# ProPrj___2024-09-21_20-05-29_2024-09-27.net
KiCad netlist of a schematic drawn in EasyEDA Pro
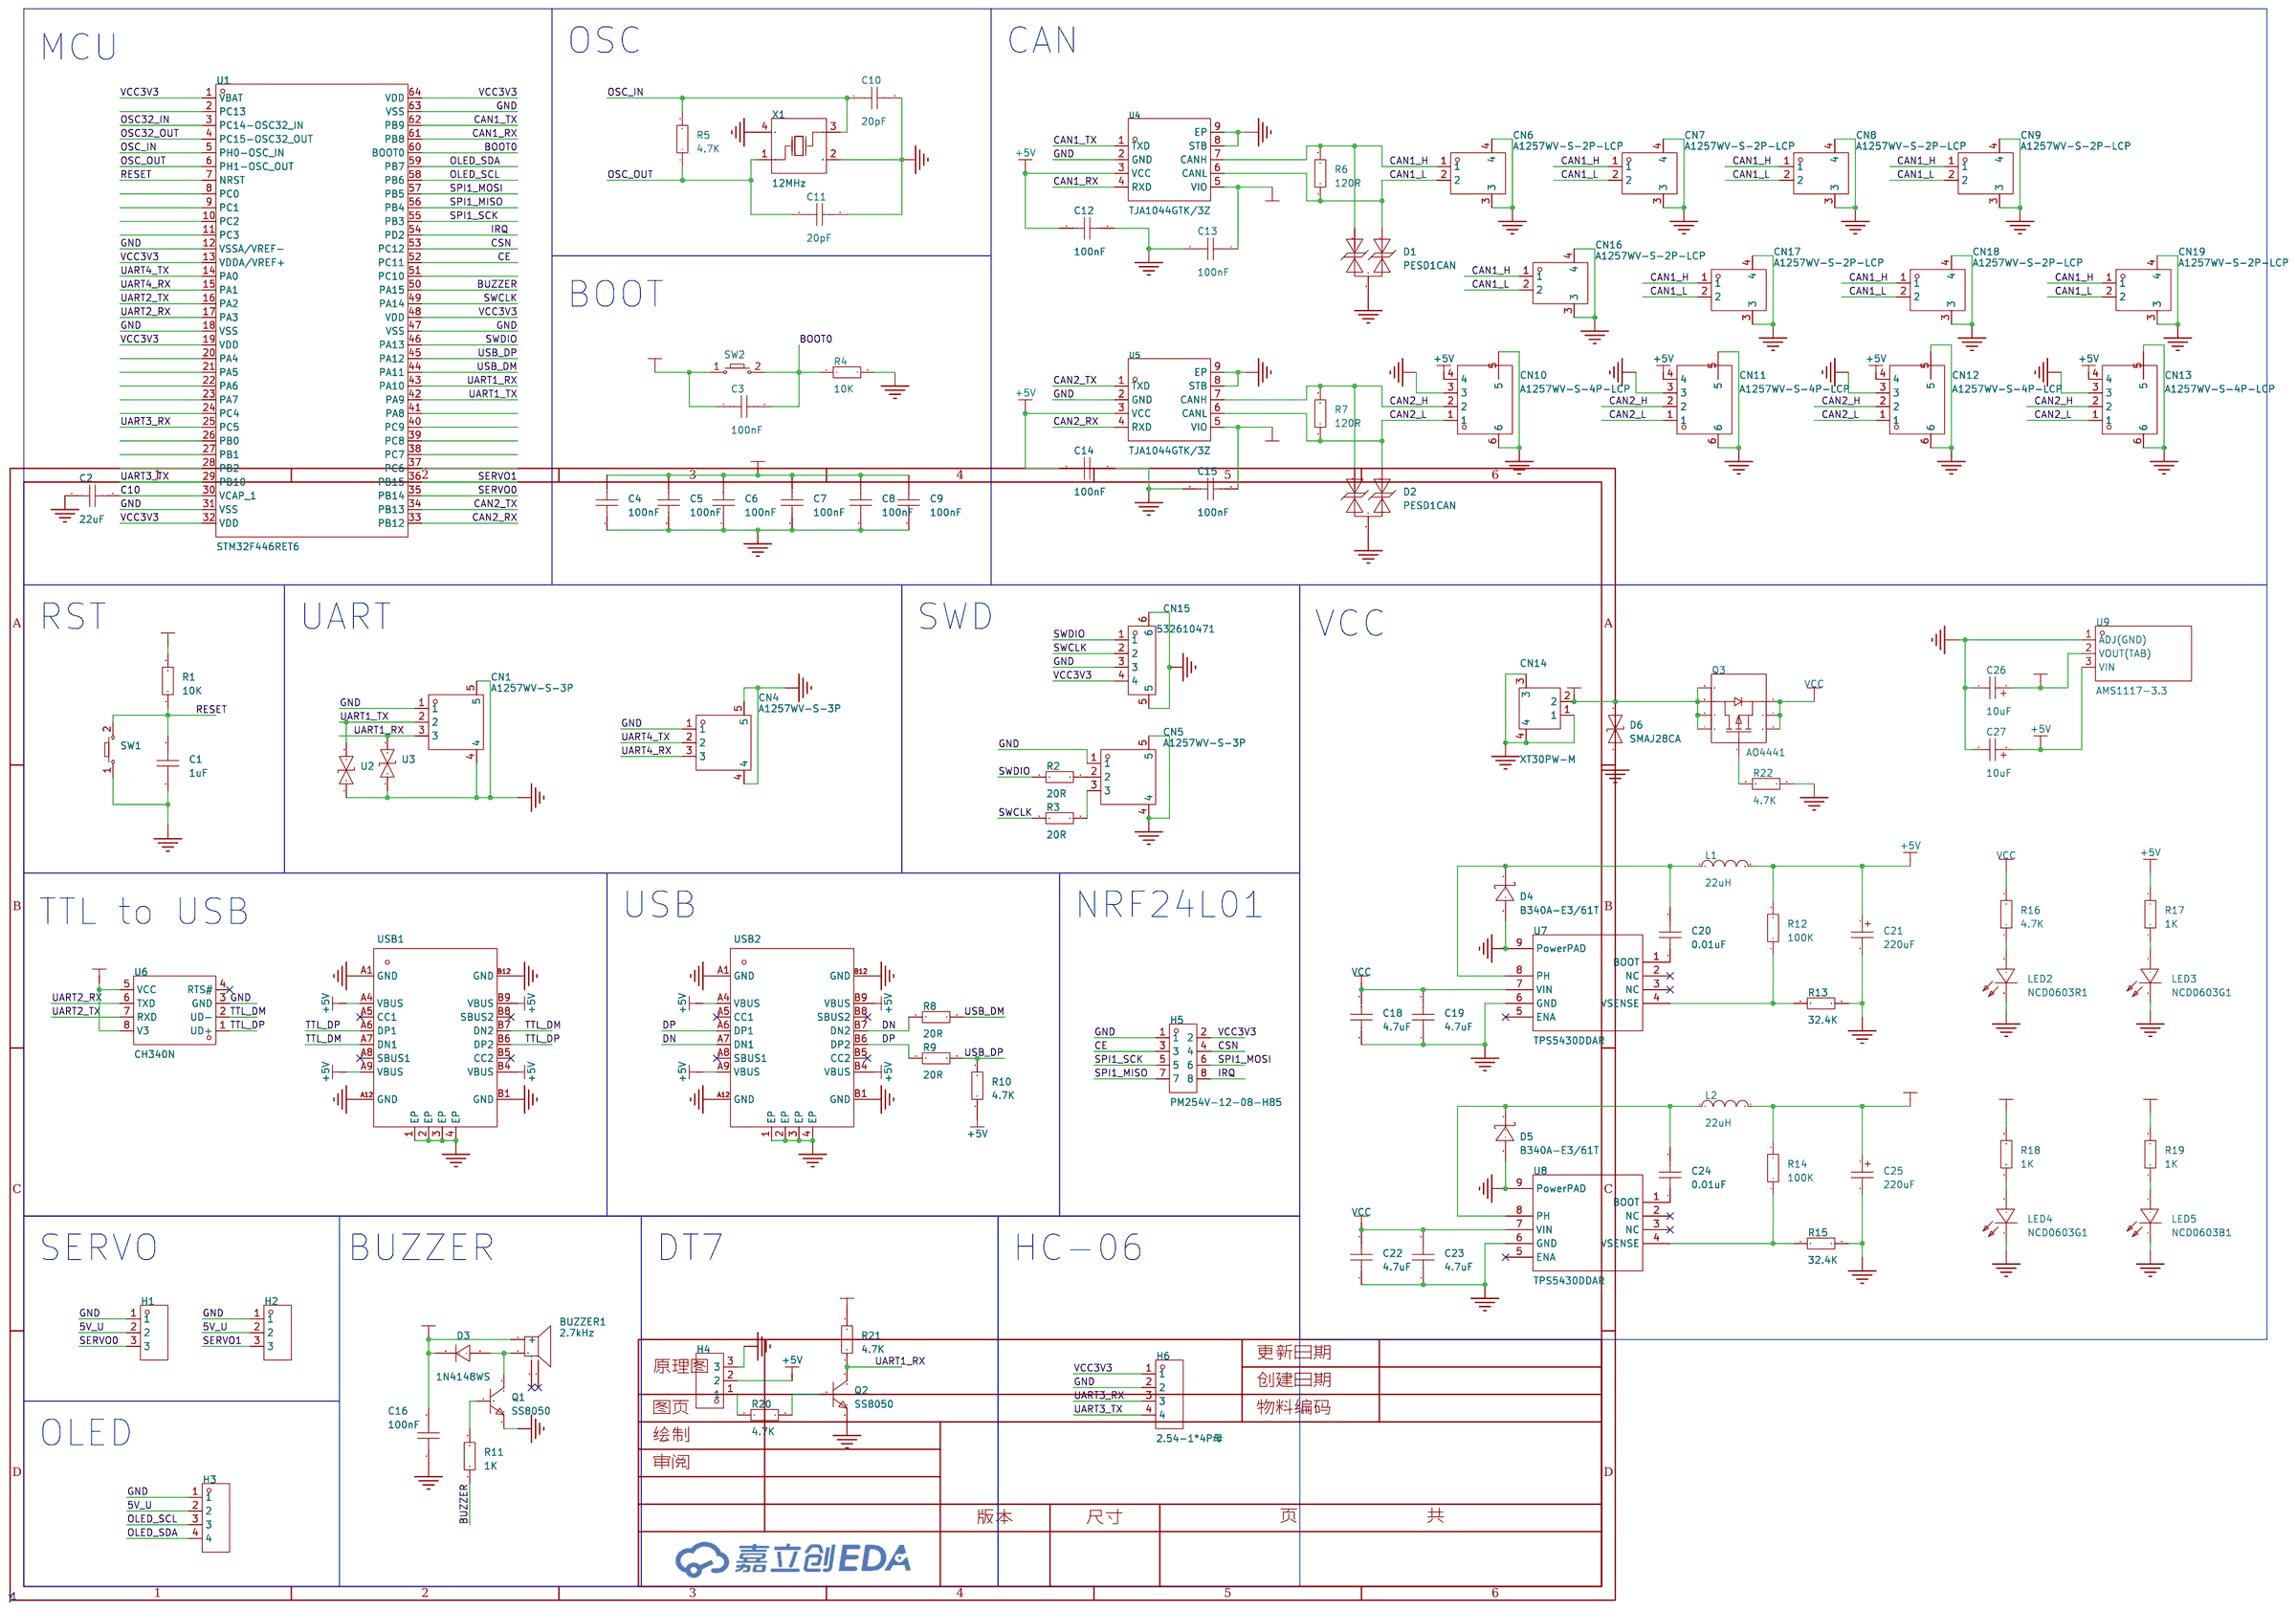
[diagram p0: schematic sheet]

(export (version "E")
  (design (tool "Eeschema 10.0.6"))
  (components
    (comp (ref "BUZZER1")
      (value "2.7kHz")
      (footprint "easyedapro:BUZ-SMD_4P-L8.5-W8.5-P8.50-BR")
      (description "驱动方式:无源(外部驱动);构造类型:电磁式;频率:2.7kHz;声压(SPL):80dB@5V,10cm;")
      (fields (field (name "Manufacturer Part") "MLT-8530") (field (name "Manufacturer") "华能"))
      (libsource (lib "easyedapro") (part "MLT-8530"))
    )
    (comp (ref "C1")
      (value "1uF")
      (footprint "easyedapro:C0603")
      (libsource (lib "easyedapro") (part "CapAcitance"))
    )
    (comp (ref "C2")
      (value "22uF")
      (footprint "easyedapro:C0603")
      (libsource (lib "easyedapro") (part "CapAcitance"))
    )
    (comp (ref "C3")
      (value "100nF")
      (footprint "easyedapro:C0603")
      (libsource (lib "easyedapro") (part "CapAcitance"))
    )
    (comp (ref "C4")
      (value "100nF")
      (footprint "easyedapro:C0603")
      (libsource (lib "easyedapro") (part "CapAcitance"))
    )
    (comp (ref "C5")
      (value "100nF")
      (footprint "easyedapro:C0603")
      (libsource (lib "easyedapro") (part "CapAcitance"))
    )
    (comp (ref "C6")
      (value "100nF")
      (footprint "easyedapro:C0603")
      (libsource (lib "easyedapro") (part "CapAcitance"))
    )
    (comp (ref "C7")
      (value "100nF")
      (footprint "easyedapro:C0603")
      (libsource (lib "easyedapro") (part "CapAcitance"))
    )
    (comp (ref "C8")
      (value "100nF")
      (footprint "easyedapro:C0603")
      (libsource (lib "easyedapro") (part "CapAcitance"))
    )
    (comp (ref "C9")
      (value "100nF")
      (footprint "easyedapro:C0603")
      (libsource (lib "easyedapro") (part "CapAcitance"))
    )
    (comp (ref "C10")
      (value "20pF")
      (footprint "easyedapro:C0603")
      (libsource (lib "easyedapro") (part "CapAcitance"))
    )
    (comp (ref "C11")
      (value "20pF")
      (footprint "easyedapro:C0603")
      (libsource (lib "easyedapro") (part "CapAcitance"))
    )
    (comp (ref "C12")
      (value "100nF")
      (footprint "easyedapro:C0603")
      (libsource (lib "easyedapro") (part "CapAcitance"))
    )
    (comp (ref "C13")
      (value "100nF")
      (footprint "easyedapro:C0603")
      (libsource (lib "easyedapro") (part "CapAcitance"))
    )
    (comp (ref "C14")
      (value "100nF")
      (footprint "easyedapro:C0603")
      (libsource (lib "easyedapro") (part "CapAcitance"))
    )
    (comp (ref "C15")
      (value "100nF")
      (footprint "easyedapro:C0603")
      (libsource (lib "easyedapro") (part "CapAcitance"))
    )
    (comp (ref "C16")
      (value "100nF")
      (footprint "easyedapro:C0603")
      (libsource (lib "easyedapro") (part "CapAcitance"))
    )
    (comp (ref "C18")
      (value "4.7uF")
      (footprint "easyedapro:C0603")
      (libsource (lib "easyedapro") (part "CapAcitance"))
    )
    (comp (ref "C19")
      (value "4.7uF")
      (footprint "easyedapro:C0603")
      (libsource (lib "easyedapro") (part "CapAcitance"))
    )
    (comp (ref "C20")
      (value "0.01uF")
      (footprint "easyedapro:C0603")
      (libsource (lib "easyedapro") (part "CapAcitance"))
    )
    (comp (ref "C21")
      (value "220uF")
      (footprint "easyedapro:C_Ele_SMD_3x5.4mm")
      (fields
        (field (name "Manufacturer Part") "RVT220UF16V67RV0015")
        (field (name "Manufacturer") "KNSCHA(科尼盛)")
      )
      (libsource (lib "easyedapro") (part "CAP"))
    )
    (comp (ref "C22")
      (value "4.7uF")
      (footprint "easyedapro:C0603")
      (libsource (lib "easyedapro") (part "CapAcitance"))
    )
    (comp (ref "C23")
      (value "4.7uF")
      (footprint "easyedapro:C0603")
      (libsource (lib "easyedapro") (part "CapAcitance"))
    )
    (comp (ref "C24")
      (value "0.01uF")
      (footprint "easyedapro:C0603")
      (libsource (lib "easyedapro") (part "CapAcitance"))
    )
    (comp (ref "C25")
      (value "220uF")
      (footprint "easyedapro:C_Ele_SMD_3x5.4mm")
      (fields
        (field (name "Manufacturer Part") "RVT220UF16V67RV0015")
        (field (name "Manufacturer") "KNSCHA(科尼盛)")
      )
      (libsource (lib "easyedapro") (part "CAP"))
    )
    (comp (ref "C26")
      (value "10uF")
      (footprint "easyedapro:C_Ele_SMD_3x5.4mm")
      (fields
        (field (name "Manufacturer Part") "CL10A106KP8NNNC")
        (field (name "Manufacturer") "SAMSUNG(三星)")
      )
      (libsource (lib "easyedapro") (part "CAP"))
    )
    (comp (ref "C27")
      (value "10uF")
      (footprint "easyedapro:C_Ele_SMD_3x5.4mm")
      (fields
        (field (name "Manufacturer Part") "CL10A106KP8NNNC")
        (field (name "Manufacturer") "SAMSUNG(三星)")
      )
      (libsource (lib "easyedapro") (part "CAP"))
    )
    (comp (ref "CN1")
      (value "A1257WV-S-3P")
      (footprint "easyedapro:CONN-SMD_A1257WV-S-3P")
      (description "插针结构:1x3P;间距:1.25mm;安装方式:-;参考系列:GH;总PIN数:3P;排数:1;每排PIN数:3;行距:-;触头材质:黄铜;")
      (fields (field (name "Manufacturer") "CJT(长江连接器)"))
      (libsource (lib "easyedapro") (part "A1257WV-S-3P"))
    )
    (comp (ref "CN4")
      (value "A1257WV-S-3P")
      (footprint "easyedapro:CONN-SMD_A1257WV-S-3P")
      (description "插针结构:1x3P;间距:1.25mm;安装方式:-;参考系列:GH;总PIN数:3P;排数:1;每排PIN数:3;行距:-;触头材质:黄铜;")
      (fields (field (name "Manufacturer") "CJT(长江连接器)"))
      (libsource (lib "easyedapro") (part "A1257WV-S-3P"))
    )
    (comp (ref "CN5")
      (value "A1257WV-S-3P")
      (footprint "easyedapro:CONN-SMD_A1257WV-S-3P")
      (description "插针结构:1x3P;间距:1.25mm;安装方式:-;参考系列:GH;总PIN数:3P;排数:1;每排PIN数:3;行距:-;触头材质:黄铜;")
      (fields (field (name "Manufacturer") "CJT(长江连接器)"))
      (libsource (lib "easyedapro") (part "A1257WV-S-3P"))
    )
    (comp (ref "CN6")
      (value "A1257WV-S-2P-LCP")
      (footprint "easyedapro:CONN-SMD_A1257WR-S-2P")
      (description "插针结构:1x2P;间距:1.25mm;安装方式:-;参考系列:GH;总PIN数:2P;排数:1;每排PIN数:2;行距:-;触头材质:黄铜;")
      (fields (field (name "Manufacturer") "CJT(长江连接器)"))
      (libsource (lib "easyedapro") (part "A1257WR-S-2P"))
    )
    (comp (ref "CN7")
      (value "A1257WV-S-2P-LCP")
      (footprint "easyedapro:CONN-SMD_A1257WR-S-2P")
      (description "插针结构:1x2P;间距:1.25mm;安装方式:-;参考系列:GH;总PIN数:2P;排数:1;每排PIN数:2;行距:-;触头材质:黄铜;")
      (fields (field (name "Manufacturer") "CJT(长江连接器)"))
      (libsource (lib "easyedapro") (part "A1257WR-S-2P"))
    )
    (comp (ref "CN8")
      (value "A1257WV-S-2P-LCP")
      (footprint "easyedapro:CONN-SMD_A1257WR-S-2P")
      (description "插针结构:1x2P;间距:1.25mm;安装方式:-;参考系列:GH;总PIN数:2P;排数:1;每排PIN数:2;行距:-;触头材质:黄铜;")
      (fields (field (name "Manufacturer") "CJT(长江连接器)"))
      (libsource (lib "easyedapro") (part "A1257WR-S-2P"))
    )
    (comp (ref "CN9")
      (value "A1257WV-S-2P-LCP")
      (footprint "easyedapro:CONN-SMD_A1257WR-S-2P")
      (description "插针结构:1x2P;间距:1.25mm;安装方式:-;参考系列:GH;总PIN数:2P;排数:1;每排PIN数:2;行距:-;触头材质:黄铜;")
      (fields (field (name "Manufacturer") "CJT(长江连接器)"))
      (libsource (lib "easyedapro") (part "A1257WR-S-2P"))
    )
    (comp (ref "CN10")
      (value "A1257WV-S-4P-LCP")
      (footprint "easyedapro:CONN-SMD_A1257WR-S-4P")
      (description "插针结构:1x4P;间距:1.25mm;安装方式:-;参考系列:GH;总PIN数:4P;排数:1;每排PIN数:4;行距:-;触头材质:黄铜;")
      (fields (field (name "Manufacturer") "CJT(长江连接器)"))
      (libsource (lib "easyedapro") (part "A1257WR-S-4P"))
    )
    (comp (ref "CN11")
      (value "A1257WV-S-4P-LCP")
      (footprint "easyedapro:CONN-SMD_A1257WR-S-4P")
      (description "插针结构:1x4P;间距:1.25mm;安装方式:-;参考系列:GH;总PIN数:4P;排数:1;每排PIN数:4;行距:-;触头材质:黄铜;")
      (fields (field (name "Manufacturer") "CJT(长江连接器)"))
      (libsource (lib "easyedapro") (part "A1257WR-S-4P"))
    )
    (comp (ref "CN12")
      (value "A1257WV-S-4P-LCP")
      (footprint "easyedapro:CONN-SMD_A1257WR-S-4P")
      (description "插针结构:1x4P;间距:1.25mm;安装方式:-;参考系列:GH;总PIN数:4P;排数:1;每排PIN数:4;行距:-;触头材质:黄铜;")
      (fields (field (name "Manufacturer") "CJT(长江连接器)"))
      (libsource (lib "easyedapro") (part "A1257WR-S-4P"))
    )
    (comp (ref "CN13")
      (value "A1257WV-S-4P-LCP")
      (footprint "easyedapro:CONN-SMD_A1257WR-S-4P")
      (description "插针结构:1x4P;间距:1.25mm;安装方式:-;参考系列:GH;总PIN数:4P;排数:1;每排PIN数:4;行距:-;触头材质:黄铜;")
      (fields (field (name "Manufacturer") "CJT(长江连接器)"))
      (libsource (lib "easyedapro") (part "A1257WR-S-4P"))
    )
    (comp (ref "CN14")
      (value "XT30PW-M")
      (footprint "easyedapro:CONN-TH_XT30PW-M")
      (description "类别:-;类型1:-;")
      (fields (field (name "Manufacturer") "AMASS(艾迈斯)"))
      (libsource (lib "easyedapro") (part "XT30PW-M"))
    )
    (comp (ref "CN15")
      (value "532610471")
      (footprint "easyedapro:CONN-SMD_4P-P1.25_53261-0471")
      (fields (field (name "Manufacturer") "MOLEX"))
      (libsource (lib "easyedapro") (part "532610471_C696092"))
    )
    (comp (ref "CN16")
      (value "A1257WV-S-2P-LCP")
      (footprint "easyedapro:CONN-SMD_A1257WR-S-2P")
      (description "插针结构:1x2P;间距:1.25mm;安装方式:-;参考系列:GH;总PIN数:2P;排数:1;每排PIN数:2;行距:-;触头材质:黄铜;")
      (fields (field (name "Manufacturer") "CJT(长江连接器)"))
      (libsource (lib "easyedapro") (part "A1257WR-S-2P"))
    )
    (comp (ref "CN17")
      (value "A1257WV-S-2P-LCP")
      (footprint "easyedapro:CONN-SMD_A1257WR-S-2P")
      (description "插针结构:1x2P;间距:1.25mm;安装方式:-;参考系列:GH;总PIN数:2P;排数:1;每排PIN数:2;行距:-;触头材质:黄铜;")
      (fields (field (name "Manufacturer") "CJT(长江连接器)"))
      (libsource (lib "easyedapro") (part "A1257WR-S-2P"))
    )
    (comp (ref "CN18")
      (value "A1257WV-S-2P-LCP")
      (footprint "easyedapro:CONN-SMD_A1257WR-S-2P")
      (description "插针结构:1x2P;间距:1.25mm;安装方式:-;参考系列:GH;总PIN数:2P;排数:1;每排PIN数:2;行距:-;触头材质:黄铜;")
      (fields (field (name "Manufacturer") "CJT(长江连接器)"))
      (libsource (lib "easyedapro") (part "A1257WR-S-2P"))
    )
    (comp (ref "CN19")
      (value "A1257WV-S-2P-LCP")
      (footprint "easyedapro:CONN-SMD_A1257WR-S-2P")
      (description "插针结构:1x2P;间距:1.25mm;安装方式:-;参考系列:GH;总PIN数:2P;排数:1;每排PIN数:2;行距:-;触头材质:黄铜;")
      (fields (field (name "Manufacturer") "CJT(长江连接器)"))
      (libsource (lib "easyedapro") (part "A1257WR-S-2P"))
    )
    (comp (ref "D1")
      (value "PESD1CAN")
      (footprint "easyedapro:SOT-23-3_L2.9-W1.6-P1.90-LS2.8-BR")
      (description "极性:双向;反向截止电压(Vrwm):24V;最大钳位电压:48V;峰值脉冲电流(Ipp)@10/1000us:6A;击穿电压:26.7V;")
      (fields (field (name "Manufacturer") "BORN(伯恩半导体)"))
      (libsource (lib "easyedapro") (part "PESD1CAN_C343993"))
    )
    (comp (ref "D2")
      (value "PESD1CAN")
      (footprint "easyedapro:SOT-23-3_L2.9-W1.6-P1.90-LS2.8-BR")
      (description "极性:双向;反向截止电压(Vrwm):24V;最大钳位电压:48V;峰值脉冲电流(Ipp)@10/1000us:6A;击穿电压:26.7V;")
      (fields (field (name "Manufacturer") "BORN(伯恩半导体)"))
      (libsource (lib "easyedapro") (part "PESD1CAN_C343993"))
    )
    (comp (ref "D3")
      (value "1N4148WS")
      (footprint "easyedapro:SOD-323_L1.8-W1.3-LS2.5-RD")
      (description "二极管配置:独立式;正向压降(Vf):1.25V@150mA;直流反向耐压(Vr):100V;平均整流电流(Io):150mA;功率:200mW;反向恢复时间(trr):4ns;")
      (fields (field (name "Manufacturer") "CJ(江苏长电/长晶)"))
      (libsource (lib "easyedapro") (part "1N4148WS T4"))
    )
    (comp (ref "D4")
      (value "B340A-E3/61T")
      (footprint "easyedapro:SMA_L4.3-W2.6-LS5.2-RD")
      (description "正向压降(Vf):550mV@3A;直流反向耐压(Vr):40V;平均整流电流(Io):3A;")
      (fields (field (name "Manufacturer") "VISHAY(威世)"))
      (libsource (lib "easyedapro") (part "B340A-E3/61T"))
    )
    (comp (ref "D5")
      (value "B340A-E3/61T")
      (footprint "easyedapro:SMA_L4.3-W2.6-LS5.2-RD")
      (description "正向压降(Vf):550mV@3A;直流反向耐压(Vr):40V;平均整流电流(Io):3A;")
      (fields (field (name "Manufacturer") "VISHAY(威世)"))
      (libsource (lib "easyedapro") (part "B340A-E3/61T"))
    )
    (comp (ref "D6")
      (value "SMAJ28CA")
      (footprint "easyedapro:SMA_L4.4-W2.6-LS5.0-BI")
      (description "反向截止电压(Vrwm):28V;最大钳位电压:45.4V;峰值脉冲电流(Ipp)@10/1000us:8.8A;峰值脉冲功率(Ppp)@10/1000us:400W;击穿电压:31.1V;")
      (fields (field (name "Manufacturer") "Littelfuse(美国力特)"))
      (libsource (lib "easyedapro") (part "SMAJ28CA-C148228"))
    )
    (comp (ref "H1")
      (value "2.54-1*3P针")
      (fields (field (name "Manufacturer") "BOOMELE(博穆精密)"))
      (libsource (lib "easyedapro") (part "PM254V-11-03-H85"))
    )
    (comp (ref "H2")
      (value "2.54-1*3P针")
      (fields (field (name "Manufacturer") "BOOMELE(博穆精密)"))
      (libsource (lib "easyedapro") (part "PM254V-11-03-H85"))
    )
    (comp (ref "H3")
      (value "2.54-1*4P母")
      (footprint "easyedapro:HDR-TH_4P-P2.54-V-F")
      (fields (field (name "Manufacturer") "BOOMELE(博穆精密)"))
      (libsource (lib "easyedapro") (part "2.54-1*4P母"))
    )
    (comp (ref "H4")
      (value "2.54-1*3P针")
      (fields (field (name "Manufacturer") "BOOMELE(博穆精密)"))
      (libsource (lib "easyedapro") (part "PM254V-11-03-H85"))
    )
    (comp (ref "H5")
      (value "PM254V-12-08-H85")
      (footprint "easyedapro:HDR-TH_8P-P2.54-V-F-R2-C4-S2.54")
      (fields (field (name "Manufacturer") "XFCN(兴飞)"))
      (libsource (lib "easyedapro") (part "PM254V-12-08-H85_C2834799"))
    )
    (comp (ref "H6")
      (value "2.54-1*4P母")
      (footprint "easyedapro:HDR-TH_4P-P2.54-V-F")
      (fields (field (name "Manufacturer") "BOOMELE(博穆精密)"))
      (libsource (lib "easyedapro") (part "2.54-1*4P母"))
    )
    (comp (ref "L1")
      (value "22uH")
      (footprint "easyedapro:IND-SMD_L7.0-W6.6_FXL0630")
      (description "电感值:22uH;精度:±20%;额定电流:2.5A;饱和电流(Isat):3A;类型:一体成型电感;")
      (fields (field (name "Manufacturer Part") "FXL0630-220-M") (field (name "Manufacturer") "cjiang(长江微电)"))
      (libsource (lib "easyedapro") (part "FXL0630-220-M"))
    )
    (comp (ref "L2")
      (value "22uH")
      (footprint "easyedapro:IND-SMD_L7.0-W6.6_FXL0630")
      (description "电感值:22uH;精度:±20%;额定电流:2.5A;饱和电流(Isat):3A;类型:一体成型电感;")
      (fields (field (name "Manufacturer Part") "FXL0630-220-M") (field (name "Manufacturer") "cjiang(长江微电)"))
      (libsource (lib "easyedapro") (part "FXL0630-220-M"))
    )
    (comp (ref "LED2")
      (value "NCD0603R1")
      (footprint "easyedapro:LED0805-R-RD")
      (fields (field (name "Manufacturer") "国星光电"))
      (libsource (lib "easyedapro") (part "FC-2012HRK-620D"))
    )
    (comp (ref "LED3")
      (value "NCD0603G1")
      (footprint "easyedapro:LED0805-R-RD")
      (fields (field (name "Manufacturer") "国星光电"))
      (libsource (lib "easyedapro") (part "FC-2012HRK-620D"))
    )
    (comp (ref "LED4")
      (value "NCD0603G1")
      (footprint "easyedapro:LED0805-R-RD")
      (fields (field (name "Manufacturer") "国星光电"))
      (libsource (lib "easyedapro") (part "FC-2012HRK-620D"))
    )
    (comp (ref "LED5")
      (value "NCD0603B1")
      (footprint "easyedapro:LED0805-R-RD")
      (fields (field (name "Manufacturer") "国星光电"))
      (libsource (lib "easyedapro") (part "FC-2012HRK-620D"))
    )
    (comp (ref "Q1")
      (value "SS8050")
      (footprint "easyedapro:SOT-23-3_L2.9-W1.3-P1.90-LS2.4-BR")
      (description "晶体管类型:NPN;集电极电流(Ic):1.5A;集射极击穿电压(Vceo):25V;功率(Pd):300mW;直流电流增益(hFE@Ic,Vce):200@100mA,1V;")
      (fields (field (name "Manufacturer") "CJ(江苏长电/长晶)"))
      (libsource (lib "easyedapro") (part "SS8050_C2150"))
    )
    (comp (ref "Q2")
      (value "SS8050")
      (footprint "easyedapro:SOT-23-3_L2.9-W1.3-P1.90-LS2.4-BR")
      (description "晶体管类型:NPN;集电极电流(Ic):1.5A;集射极击穿电压(Vceo):25V;功率(Pd):300mW;直流电流增益(hFE@Ic,Vce):200@100mA,1V;")
      (fields (field (name "Manufacturer") "CJ(江苏长电/长晶)"))
      (libsource (lib "easyedapro") (part "SS8050_C2150"))
    )
    (comp (ref "Q3")
      (value "AO4441")
      (footprint "easyedapro:SOIC-8_L4.9-W3.9-P1.27-LS6.0-BL")
      (fields (field (name "Manufacturer") "AOS"))
      (libsource (lib "easyedapro") (part "AO4441"))
    )
    (comp (ref "R1") (value "10K") (footprint "easyedapro:R0603") (libsource (lib "easyedapro") (part "电阻")))
    (comp (ref "R2") (value "20R") (footprint "easyedapro:R0603") (libsource (lib "easyedapro") (part "电阻")))
    (comp (ref "R3") (value "20R") (footprint "easyedapro:R0603") (libsource (lib "easyedapro") (part "电阻")))
    (comp (ref "R4") (value "10K") (footprint "easyedapro:R0603") (libsource (lib "easyedapro") (part "电阻")))
    (comp (ref "R5") (value "4.7K") (footprint "easyedapro:R0603") (libsource (lib "easyedapro") (part "电阻")))
    (comp (ref "R6") (value "120R") (footprint "easyedapro:R0603") (libsource (lib "easyedapro") (part "电阻")))
    (comp (ref "R7") (value "120R") (footprint "easyedapro:R0603") (libsource (lib "easyedapro") (part "电阻")))
    (comp (ref "R8") (value "20R") (footprint "easyedapro:R0603") (libsource (lib "easyedapro") (part "电阻")))
    (comp (ref "R9") (value "20R") (footprint "easyedapro:R0603") (libsource (lib "easyedapro") (part "电阻")))
    (comp (ref "R10")
      (value "4.7K")
      (footprint "easyedapro:R0603")
      (libsource (lib "easyedapro") (part "电阻"))
    )
    (comp (ref "R11") (value "1K") (footprint "easyedapro:R0603") (libsource (lib "easyedapro") (part "电阻")))
    (comp (ref "R12")
      (value "100K")
      (footprint "easyedapro:R0603")
      (libsource (lib "easyedapro") (part "电阻"))
    )
    (comp (ref "R13")
      (value "32.4K")
      (footprint "easyedapro:R0603")
      (libsource (lib "easyedapro") (part "电阻"))
    )
    (comp (ref "R14")
      (value "100K")
      (footprint "easyedapro:R0603")
      (libsource (lib "easyedapro") (part "电阻"))
    )
    (comp (ref "R15")
      (value "32.4K")
      (footprint "easyedapro:R0603")
      (libsource (lib "easyedapro") (part "电阻"))
    )
    (comp (ref "R16")
      (value "4.7K")
      (footprint "easyedapro:R0603")
      (libsource (lib "easyedapro") (part "电阻"))
    )
    (comp (ref "R17") (value "1K") (footprint "easyedapro:R0603") (libsource (lib "easyedapro") (part "电阻")))
    (comp (ref "R18") (value "1K") (footprint "easyedapro:R0603") (libsource (lib "easyedapro") (part "电阻")))
    (comp (ref "R19") (value "1K") (footprint "easyedapro:R0603") (libsource (lib "easyedapro") (part "电阻")))
    (comp (ref "R20")
      (value "4.7K")
      (footprint "easyedapro:R0603")
      (libsource (lib "easyedapro") (part "电阻"))
    )
    (comp (ref "R21")
      (value "4.7K")
      (footprint "easyedapro:R0603")
      (libsource (lib "easyedapro") (part "电阻"))
    )
    (comp (ref "R22")
      (value "4.7K")
      (footprint "easyedapro:R0603")
      (libsource (lib "easyedapro") (part "电阻"))
    )
    (comp (ref "SW1")
      (value "~")
      (footprint "easyedapro:Key_SMD_3x4x2")
      (libsource (lib "easyedapro") (part "轻触按键x2"))
    )
    (comp (ref "SW2")
      (value "~")
      (footprint "easyedapro:Key_SMD_3x4x2")
      (libsource (lib "easyedapro") (part "轻触按键x2"))
    )
    (comp (ref "U1")
      (value "STM32F446RET6")
      (footprint "easyedapro:LQFP-64_L10.0-W10.0-P0.50-LS12.0-BL")
      (description "CPU内核:CM4;程序存储容量:512KB;RAM总容量:128KB;GPIO端口数量:50;工作电压范围:1.7V~3.6V;CPU最大主频:180MHz;程序存储器类型:FLASH;")
      (fields (field (name "Manufacturer") "ST(意法半导体)"))
      (libsource (lib "easyedapro") (part "STM32F446RET6"))
    )
    (comp (ref "U2")
      (value "ESD9B5.0ST5G")
      (footprint "easyedapro:SOD-923_L0.8-W0.6-LS1.0-BI")
      (fields (field (name "Manufacturer") "TECH PUBLIC(台舟)"))
      (libsource (lib "easyedapro") (part "ESD9B5.0ST5G_C3021104"))
    )
    (comp (ref "U3")
      (value "ESD9B5.0ST5G")
      (footprint "easyedapro:SOD-923_L0.8-W0.6-LS1.0-BI")
      (fields (field (name "Manufacturer") "TECH PUBLIC(台舟)"))
      (libsource (lib "easyedapro") (part "ESD9B5.0ST5G_C3021104"))
    )
    (comp (ref "U4")
      (value "TJA1044GTK/3Z")
      (footprint "easyedapro:HVSON-8_L3.0-W3.0-P0.65-BL-EP")
      (description "类型:-;")
      (fields (field (name "Manufacturer") "NXP(恩智浦)"))
      (libsource (lib "easyedapro") (part "TJA1044GTK/3Z"))
    )
    (comp (ref "U5")
      (value "TJA1044GTK/3Z")
      (footprint "easyedapro:HVSON-8_L3.0-W3.0-P0.65-BL-EP")
      (description "类型:-;")
      (fields (field (name "Manufacturer") "NXP(恩智浦)"))
      (libsource (lib "easyedapro") (part "TJA1044GTK/3Z"))
    )
    (comp (ref "U6")
      (value "CH340N")
      (footprint "easyedapro:SOP-8_L4.9-W3.9-P1.27-LS6.0-BL")
      (fields (field (name "Manufacturer") "WCH(南京沁恒)"))
      (libsource (lib "easyedapro") (part "CH340N_C2977777"))
    )
    (comp (ref "U7")
      (value "TPS5430DDAR")
      (footprint "easyedapro:ESOP-8_L4.9-W3.9-P1.27-LS6.0-TL-EP")
      (description "功能类型:降压型;输出类型:可调;输入电压:5.5V~36V;输出电压:1.221V~32.04V;输出电流(最大值):3A;")
      (fields (field (name "Manufacturer") "TI(德州仪器)"))
      (libsource (lib "easyedapro") (part "TPS5430DDAR"))
    )
    (comp (ref "U8")
      (value "TPS5430DDAR")
      (footprint "easyedapro:ESOP-8_L4.9-W3.9-P1.27-LS6.0-TL-EP")
      (description "功能类型:降压型;输出类型:可调;输入电压:5.5V~36V;输出电压:1.221V~32.04V;输出电流(最大值):3A;")
      (fields (field (name "Manufacturer") "TI(德州仪器)"))
      (libsource (lib "easyedapro") (part "TPS5430DDAR"))
    )
    (comp (ref "U9")
      (value "AMS1117-3.3")
      (footprint "easyedapro:SOT-89_L4.5-W2.5-P1.50-LS4.2-BR")
      (description "输出类型:固定;最大输入电压:12V;输出电压:3.3V;最大输出电流:1A;电源纹波抑制比(PSRR):60dB@(120Hz);输出极性:正极;")
      (fields (field (name "Manufacturer") "UMW(友台半导体)"))
      (libsource (lib "easyedapro") (part "AMS1117-3.3_C347256"))
    )
    (comp (ref "USB1")
      (value "~")
      (footprint "easyedapro:USB_TYPE-C-16P")
      (libsource (lib "easyedapro") (part "USB_TYPE-C-16P"))
    )
    (comp (ref "USB2")
      (value "~")
      (footprint "easyedapro:USB_TYPE-C-16P")
      (libsource (lib "easyedapro") (part "USB_TYPE-C-16P"))
    )
    (comp (ref "X1")
      (value "12MHz")
      (footprint "easyedapro:OSC-SMD_4P-L3.2-W2.5-BL")
      (description "晶振类型:贴片晶振;频率:12MHz;常温频差:±10ppm;外接负载电容:20pF;频率稳定度(全温):±20ppm;")
      (fields (field (name "Manufacturer Part") "X322512MSB4SI") (field (name "Manufacturer") "YXC(扬兴晶振)"))
      (libsource (lib "easyedapro") (part "X322512MSB4SI"))
    )
  )
  (nets
    (net (code "1") (name "+5V") (class "Default")
      (node (ref "C12") (pin "2") (pinfunction "2_2") (pintype "input"))
      (node (ref "C14") (pin "2") (pinfunction "2_2") (pintype "input"))
      (node (ref "C21") (pin "1") (pinfunction "1_1") (pintype "input"))
      (node (ref "C27") (pin "1") (pinfunction "1_1") (pintype "input"))
      (node (ref "CN10") (pin "4") (pinfunction "4_4") (pintype "unspecified"))
      (node (ref "CN11") (pin "4") (pinfunction "4_4") (pintype "unspecified"))
      (node (ref "CN12") (pin "4") (pinfunction "4_4") (pintype "unspecified"))
      (node (ref "CN13") (pin "4") (pinfunction "4_4") (pintype "unspecified"))
      (node (ref "H4") (pin "2") (pinfunction "2_2") (pintype "unspecified"))
      (node (ref "L1") (pin "2") (pinfunction "2_2") (pintype "unspecified"))
      (node (ref "R10") (pin "1") (pinfunction "1_1") (pintype "input"))
      (node (ref "R12") (pin "2") (pinfunction "2_2") (pintype "input"))
      (node (ref "R17") (pin "2") (pinfunction "2_2") (pintype "input"))
      (node (ref "U4") (pin "3") (pinfunction "VCC_3") (pintype "input"))
      (node (ref "U5") (pin "3") (pinfunction "VCC_3") (pintype "input"))
      (node (ref "U9") (pin "3") (pinfunction "VIN_3") (pintype "unspecified"))
      (node (ref "USB1") (pin "A4") (pinfunction "VBUS_A4") (pintype "input"))
      (node (ref "USB1") (pin "A9") (pinfunction "VBUS_A9") (pintype "input"))
      (node (ref "USB1") (pin "B4") (pinfunction "VBUS_B4") (pintype "input"))
      (node (ref "USB1") (pin "B9") (pinfunction "VBUS_B9") (pintype "input"))
      (node (ref "USB2") (pin "A4") (pinfunction "VBUS_A4") (pintype "input"))
      (node (ref "USB2") (pin "A9") (pinfunction "VBUS_A9") (pintype "input"))
      (node (ref "USB2") (pin "B4") (pinfunction "VBUS_B4") (pintype "input"))
      (node (ref "USB2") (pin "B9") (pinfunction "VBUS_B9") (pintype "input"))
    )
    (net (code "2") (name "/BOOT0") (class "Default")
      (node (ref "C3") (pin "2") (pinfunction "2_2") (pintype "input"))
      (node (ref "R4") (pin "1") (pinfunction "1_1") (pintype "input"))
      (node (ref "SW2") (pin "2") (pinfunction "2_2") (pintype "input"))
      (node (ref "U1") (pin "60") (pinfunction "BOOT0_60") (pintype "unspecified"))
    )
    (net (code "3") (name "/BUZZER") (class "Default")
      (node (ref "R11") (pin "1") (pinfunction "1_1") (pintype "input"))
      (node (ref "U1") (pin "50") (pinfunction "PA15_50") (pintype "unspecified"))
    )
    (net (code "4") (name "/C10") (class "Default")
      (node (ref "C2") (pin "2") (pinfunction "2_2") (pintype "input"))
      (node (ref "U1") (pin "30") (pinfunction "VCAP_1_30") (pintype "unspecified"))
    )
    (net (code "5") (name "/CAN1_H") (class "Default")
      (node (ref "CN16") (pin "1") (pinfunction "1_1") (pintype "unspecified"))
      (node (ref "CN17") (pin "1") (pinfunction "1_1") (pintype "unspecified"))
      (node (ref "CN18") (pin "1") (pinfunction "1_1") (pintype "unspecified"))
      (node (ref "CN19") (pin "1") (pinfunction "1_1") (pintype "unspecified"))
      (node (ref "CN6") (pin "1") (pinfunction "1_1") (pintype "unspecified"))
      (node (ref "CN7") (pin "1") (pinfunction "1_1") (pintype "unspecified"))
      (node (ref "CN8") (pin "1") (pinfunction "1_1") (pintype "unspecified"))
      (node (ref "CN9") (pin "1") (pinfunction "1_1") (pintype "unspecified"))
      (node (ref "D1") (pin "2") (pinfunction "K_2") (pintype "unspecified"))
      (node (ref "R6") (pin "2") (pinfunction "2_2") (pintype "input"))
      (node (ref "U4") (pin "7") (pinfunction "CANH_7") (pintype "input"))
    )
    (net (code "6") (name "/CAN1_L") (class "Default")
      (node (ref "CN16") (pin "2") (pinfunction "2_2") (pintype "unspecified"))
      (node (ref "CN17") (pin "2") (pinfunction "2_2") (pintype "unspecified"))
      (node (ref "CN18") (pin "2") (pinfunction "2_2") (pintype "unspecified"))
      (node (ref "CN19") (pin "2") (pinfunction "2_2") (pintype "unspecified"))
      (node (ref "CN6") (pin "2") (pinfunction "2_2") (pintype "unspecified"))
      (node (ref "CN7") (pin "2") (pinfunction "2_2") (pintype "unspecified"))
      (node (ref "CN8") (pin "2") (pinfunction "2_2") (pintype "unspecified"))
      (node (ref "CN9") (pin "2") (pinfunction "2_2") (pintype "unspecified"))
      (node (ref "D1") (pin "1") (pinfunction "K_1") (pintype "unspecified"))
      (node (ref "R6") (pin "1") (pinfunction "1_1") (pintype "input"))
      (node (ref "U4") (pin "6") (pinfunction "CANL_6") (pintype "input"))
    )
    (net (code "7") (name "/CAN1_RX") (class "Default")
      (node (ref "U1") (pin "61") (pinfunction "PB8_61") (pintype "unspecified"))
      (node (ref "U4") (pin "4") (pinfunction "RXD_4") (pintype "input"))
    )
    (net (code "8") (name "/CAN1_TX") (class "Default")
      (node (ref "U1") (pin "62") (pinfunction "PB9_62") (pintype "unspecified"))
      (node (ref "U4") (pin "1") (pinfunction "TXD_1") (pintype "input"))
    )
    (net (code "9") (name "/CAN2_H") (class "Default")
      (node (ref "CN10") (pin "2") (pinfunction "2_2") (pintype "unspecified"))
      (node (ref "CN11") (pin "2") (pinfunction "2_2") (pintype "unspecified"))
      (node (ref "CN12") (pin "2") (pinfunction "2_2") (pintype "unspecified"))
      (node (ref "CN13") (pin "2") (pinfunction "2_2") (pintype "unspecified"))
      (node (ref "D2") (pin "2") (pinfunction "K_2") (pintype "unspecified"))
      (node (ref "R7") (pin "2") (pinfunction "2_2") (pintype "input"))
      (node (ref "U5") (pin "7") (pinfunction "CANH_7") (pintype "input"))
    )
    (net (code "10") (name "/CAN2_L") (class "Default")
      (node (ref "CN10") (pin "1") (pinfunction "1_1") (pintype "unspecified"))
      (node (ref "CN11") (pin "1") (pinfunction "1_1") (pintype "unspecified"))
      (node (ref "CN12") (pin "1") (pinfunction "1_1") (pintype "unspecified"))
      (node (ref "CN13") (pin "1") (pinfunction "1_1") (pintype "unspecified"))
      (node (ref "D2") (pin "1") (pinfunction "K_1") (pintype "unspecified"))
      (node (ref "R7") (pin "1") (pinfunction "1_1") (pintype "input"))
      (node (ref "U5") (pin "6") (pinfunction "CANL_6") (pintype "input"))
    )
    (net (code "11") (name "/CAN2_RX") (class "Default")
      (node (ref "U1") (pin "33") (pinfunction "PB12_33") (pintype "unspecified"))
      (node (ref "U5") (pin "4") (pinfunction "RXD_4") (pintype "input"))
    )
    (net (code "12") (name "/CAN2_TX") (class "Default")
      (node (ref "U1") (pin "34") (pinfunction "PB13_34") (pintype "unspecified"))
      (node (ref "U5") (pin "1") (pinfunction "TXD_1") (pintype "input"))
    )
    (net (code "13") (name "/CE") (class "Default")
      (node (ref "H5") (pin "3") (pinfunction "3_3") (pintype "unspecified"))
      (node (ref "U1") (pin "52") (pinfunction "PC11_52") (pintype "unspecified"))
    )
    (net (code "14") (name "/CSN") (class "Default")
      (node (ref "H5") (pin "4") (pinfunction "4_4") (pintype "unspecified"))
      (node (ref "U1") (pin "53") (pinfunction "PC12_53") (pintype "unspecified"))
    )
    (net (code "15") (name "/DN") (class "Default")
      (node (ref "R8") (pin "1") (pinfunction "1_1") (pintype "input"))
      (node (ref "USB2") (pin "A7") (pinfunction "DN1_A7") (pintype "input"))
      (node (ref "USB2") (pin "B7") (pinfunction "DN2_B7") (pintype "input"))
    )
    (net (code "16") (name "/DP") (class "Default")
      (node (ref "R9") (pin "1") (pinfunction "1_1") (pintype "input"))
      (node (ref "USB2") (pin "A6") (pinfunction "DP1_A6") (pintype "input"))
      (node (ref "USB2") (pin "B6") (pinfunction "DP2_B6") (pintype "input"))
    )
    (net (code "17") (name "/IRQ") (class "Default")
      (node (ref "H5") (pin "8") (pinfunction "8_8") (pintype "unspecified"))
      (node (ref "U1") (pin "54") (pinfunction "PD2_54") (pintype "unspecified"))
    )
    (net (code "18") (name "/OLED_SCL") (class "Default")
      (node (ref "H3") (pin "3") (pinfunction "3_3") (pintype "unspecified"))
      (node (ref "U1") (pin "58") (pinfunction "PB6_58") (pintype "unspecified"))
    )
    (net (code "19") (name "/OLED_SDA") (class "Default")
      (node (ref "H3") (pin "4") (pinfunction "4_4") (pintype "unspecified"))
      (node (ref "U1") (pin "59") (pinfunction "PB7_59") (pintype "unspecified"))
    )
    (net (code "20") (name "/OSC32_IN") (class "Default")
      (node (ref "U1") (pin "3") (pinfunction "PC14-OSC32_IN_3") (pintype "unspecified"))
    )
    (net (code "21") (name "/OSC32_OUT") (class "Default")
      (node (ref "U1") (pin "4") (pinfunction "PC15-OSC32_OUT_4") (pintype "unspecified"))
    )
    (net (code "22") (name "/OSC_IN") (class "Default")
      (node (ref "C10") (pin "1") (pinfunction "1_1") (pintype "input"))
      (node (ref "R5") (pin "2") (pinfunction "2_2") (pintype "input"))
      (node (ref "U1") (pin "5") (pinfunction "PH0-OSC_IN_5") (pintype "unspecified"))
      (node (ref "X1") (pin "3") (pinfunction "OSC2_3") (pintype "unspecified"))
    )
    (net (code "23") (name "/OSC_OUT") (class "Default")
      (node (ref "C11") (pin "1") (pinfunction "1_1") (pintype "input"))
      (node (ref "R5") (pin "1") (pinfunction "1_1") (pintype "input"))
      (node (ref "U1") (pin "6") (pinfunction "PH1-OSC_OUT_6") (pintype "unspecified"))
      (node (ref "X1") (pin "1") (pinfunction "OSC1_1") (pintype "unspecified"))
    )
    (net (code "24") (name "/RESET") (class "Default")
      (node (ref "C1") (pin "1") (pinfunction "1_1") (pintype "input"))
      (node (ref "R1") (pin "1") (pinfunction "1_1") (pintype "input"))
      (node (ref "SW1") (pin "2") (pinfunction "2_2") (pintype "input"))
      (node (ref "U1") (pin "7") (pinfunction "NRST_7") (pintype "unspecified"))
    )
    (net (code "25") (name "/SERVO0") (class "Default")
      (node (ref "H1") (pin "3") (pinfunction "3_3") (pintype "unspecified"))
      (node (ref "U1") (pin "35") (pinfunction "PB14_35") (pintype "unspecified"))
    )
    (net (code "26") (name "/SERVO1") (class "Default")
      (node (ref "H2") (pin "3") (pinfunction "3_3") (pintype "unspecified"))
      (node (ref "U1") (pin "36") (pinfunction "PB15_36") (pintype "unspecified"))
    )
    (net (code "27") (name "/SPI1_MISO") (class "Default")
      (node (ref "H5") (pin "7") (pinfunction "7_7") (pintype "unspecified"))
      (node (ref "U1") (pin "56") (pinfunction "PB4_56") (pintype "unspecified"))
    )
    (net (code "28") (name "/SPI1_MOSI") (class "Default")
      (node (ref "H5") (pin "6") (pinfunction "6_6") (pintype "unspecified"))
      (node (ref "U1") (pin "57") (pinfunction "PB5_57") (pintype "unspecified"))
    )
    (net (code "29") (name "/SPI1_SCK") (class "Default")
      (node (ref "H5") (pin "5") (pinfunction "5_5") (pintype "unspecified"))
      (node (ref "U1") (pin "55") (pinfunction "PB3_55") (pintype "unspecified"))
    )
    (net (code "30") (name "/SWCLK") (class "Default")
      (node (ref "CN15") (pin "2") (pinfunction "2_2") (pintype "unspecified"))
      (node (ref "R3") (pin "1") (pinfunction "1_1") (pintype "input"))
      (node (ref "U1") (pin "49") (pinfunction "PA14_49") (pintype "unspecified"))
    )
    (net (code "31") (name "/SWDIO") (class "Default")
      (node (ref "CN15") (pin "1") (pinfunction "1_1") (pintype "unspecified"))
      (node (ref "R2") (pin "1") (pinfunction "1_1") (pintype "input"))
      (node (ref "U1") (pin "46") (pinfunction "PA13_46") (pintype "unspecified"))
    )
    (net (code "32") (name "/TTL_DM") (class "Default")
      (node (ref "U6") (pin "2") (pinfunction "UD-_2") (pintype "unspecified"))
      (node (ref "USB1") (pin "A7") (pinfunction "DN1_A7") (pintype "input"))
      (node (ref "USB1") (pin "B7") (pinfunction "DN2_B7") (pintype "input"))
    )
    (net (code "33") (name "/TTL_DP") (class "Default")
      (node (ref "U6") (pin "1") (pinfunction "UD+_1") (pintype "unspecified"))
      (node (ref "USB1") (pin "A6") (pinfunction "DP1_A6") (pintype "input"))
      (node (ref "USB1") (pin "B6") (pinfunction "DP2_B6") (pintype "input"))
    )
    (net (code "34") (name "/UART1_RX") (class "Default")
      (node (ref "CN1") (pin "3") (pinfunction "3_3") (pintype "unspecified"))
      (node (ref "Q2") (pin "3") (pinfunction "C_3") (pintype "unspecified"))
      (node (ref "R21") (pin "1") (pinfunction "1_1") (pintype "input"))
      (node (ref "U1") (pin "43") (pinfunction "PA10_43") (pintype "unspecified"))
      (node (ref "U3") (pin "2") (pinfunction "2_2") (pintype "unspecified"))
    )
    (net (code "35") (name "/UART1_TX") (class "Default")
      (node (ref "CN1") (pin "2") (pinfunction "2_2") (pintype "unspecified"))
      (node (ref "U1") (pin "42") (pinfunction "PA9_42") (pintype "unspecified"))
      (node (ref "U2") (pin "2") (pinfunction "2_2") (pintype "unspecified"))
    )
    (net (code "36") (name "/UART2_RX") (class "Default")
      (node (ref "U1") (pin "17") (pinfunction "PA3_17") (pintype "unspecified"))
      (node (ref "U6") (pin "6") (pinfunction "TXD_6") (pintype "unspecified"))
    )
    (net (code "37") (name "/UART2_TX") (class "Default")
      (node (ref "U1") (pin "16") (pinfunction "PA2_16") (pintype "unspecified"))
      (node (ref "U6") (pin "7") (pinfunction "RXD_7") (pintype "unspecified"))
    )
    (net (code "38") (name "/UART3_RX") (class "Default")
      (node (ref "H6") (pin "3") (pinfunction "3_3") (pintype "unspecified"))
      (node (ref "U1") (pin "25") (pinfunction "PC5_25") (pintype "unspecified"))
    )
    (net (code "39") (name "/UART3_TX") (class "Default")
      (node (ref "H6") (pin "4") (pinfunction "4_4") (pintype "unspecified"))
      (node (ref "U1") (pin "29") (pinfunction "PB10_29") (pintype "unspecified"))
    )
    (net (code "40") (name "/UART4_RX") (class "Default")
      (node (ref "CN4") (pin "3") (pinfunction "3_3") (pintype "unspecified"))
      (node (ref "U1") (pin "15") (pinfunction "PA1_15") (pintype "unspecified"))
    )
    (net (code "41") (name "/UART4_TX") (class "Default")
      (node (ref "CN4") (pin "2") (pinfunction "2_2") (pintype "unspecified"))
      (node (ref "U1") (pin "14") (pinfunction "PA0_14") (pintype "unspecified"))
    )
    (net (code "42") (name "/USB_DM") (class "Default")
      (node (ref "R8") (pin "2") (pinfunction "2_2") (pintype "input"))
      (node (ref "U1") (pin "44") (pinfunction "PA11_44") (pintype "unspecified"))
    )
    (net (code "43") (name "/USB_DP") (class "Default")
      (node (ref "R10") (pin "2") (pinfunction "2_2") (pintype "input"))
      (node (ref "R9") (pin "2") (pinfunction "2_2") (pintype "input"))
      (node (ref "U1") (pin "45") (pinfunction "PA12_45") (pintype "unspecified"))
    )
    (net (code "44") (name "5V_U") (class "Default")
      (node (ref "C25") (pin "1") (pinfunction "1_1") (pintype "input"))
      (node (ref "H1") (pin "2") (pinfunction "2_2") (pintype "unspecified"))
      (node (ref "H2") (pin "2") (pinfunction "2_2") (pintype "unspecified"))
      (node (ref "H3") (pin "2") (pinfunction "2_2") (pintype "unspecified"))
      (node (ref "L2") (pin "2") (pinfunction "2_2") (pintype "unspecified"))
      (node (ref "R14") (pin "2") (pinfunction "2_2") (pintype "input"))
      (node (ref "R18") (pin "2") (pinfunction "2_2") (pintype "input"))
    )
    (net (code "45") (name "BAT") (class "Default")
      (node (ref "CN14") (pin "2") (pinfunction "2_2") (pintype "unspecified"))
      (node (ref "D6") (pin "2") (pinfunction "2_2") (pintype "input"))
      (node (ref "Q3") (pin "5") (pinfunction "D_5") (pintype "unspecified"))
      (node (ref "Q3") (pin "6") (pinfunction "D_6") (pintype "unspecified"))
      (node (ref "Q3") (pin "7") (pinfunction "D_7") (pintype "unspecified"))
      (node (ref "Q3") (pin "8") (pinfunction "D_8") (pintype "unspecified"))
    )
    (net (code "46") (name "GND") (class "Default")
      (node (ref "C1") (pin "2") (pinfunction "2_2") (pintype "input"))
      (node (ref "C10") (pin "2") (pinfunction "2_2") (pintype "input"))
      (node (ref "C11") (pin "2") (pinfunction "2_2") (pintype "input"))
      (node (ref "C12") (pin "1") (pinfunction "1_1") (pintype "input"))
      (node (ref "C13") (pin "2") (pinfunction "2_2") (pintype "input"))
      (node (ref "C14") (pin "1") (pinfunction "1_1") (pintype "input"))
      (node (ref "C15") (pin "2") (pinfunction "2_2") (pintype "input"))
      (node (ref "C16") (pin "1") (pinfunction "1_1") (pintype "input"))
      (node (ref "C18") (pin "1") (pinfunction "1_1") (pintype "input"))
      (node (ref "C19") (pin "1") (pinfunction "1_1") (pintype "input"))
      (node (ref "C2") (pin "1") (pinfunction "1_1") (pintype "input"))
      (node (ref "C21") (pin "2") (pinfunction "2_2") (pintype "input"))
      (node (ref "C22") (pin "1") (pinfunction "1_1") (pintype "input"))
      (node (ref "C23") (pin "1") (pinfunction "1_1") (pintype "input"))
      (node (ref "C25") (pin "2") (pinfunction "2_2") (pintype "input"))
      (node (ref "C26") (pin "2") (pinfunction "2_2") (pintype "input"))
      (node (ref "C27") (pin "2") (pinfunction "2_2") (pintype "input"))
      (node (ref "C4") (pin "1") (pinfunction "1_1") (pintype "input"))
      (node (ref "C5") (pin "1") (pinfunction "1_1") (pintype "input"))
      (node (ref "C6") (pin "1") (pinfunction "1_1") (pintype "input"))
      (node (ref "C7") (pin "1") (pinfunction "1_1") (pintype "input"))
      (node (ref "C8") (pin "1") (pinfunction "1_1") (pintype "input"))
      (node (ref "C9") (pin "1") (pinfunction "1_1") (pintype "input"))
      (node (ref "CN1") (pin "1") (pinfunction "1_1") (pintype "unspecified"))
      (node (ref "CN1") (pin "4") (pinfunction "4_4") (pintype "unspecified"))
      (node (ref "CN1") (pin "5") (pinfunction "5_5") (pintype "unspecified"))
      (node (ref "CN10") (pin "3") (pinfunction "3_3") (pintype "unspecified"))
      (node (ref "CN10") (pin "5") (pinfunction "5_5") (pintype "unspecified"))
      (node (ref "CN10") (pin "6") (pinfunction "6_6") (pintype "unspecified"))
      (node (ref "CN11") (pin "3") (pinfunction "3_3") (pintype "unspecified"))
      (node (ref "CN11") (pin "5") (pinfunction "5_5") (pintype "unspecified"))
      (node (ref "CN11") (pin "6") (pinfunction "6_6") (pintype "unspecified"))
      (node (ref "CN12") (pin "3") (pinfunction "3_3") (pintype "unspecified"))
      (node (ref "CN12") (pin "5") (pinfunction "5_5") (pintype "unspecified"))
      (node (ref "CN12") (pin "6") (pinfunction "6_6") (pintype "unspecified"))
      (node (ref "CN13") (pin "3") (pinfunction "3_3") (pintype "unspecified"))
      (node (ref "CN13") (pin "5") (pinfunction "5_5") (pintype "unspecified"))
      (node (ref "CN13") (pin "6") (pinfunction "6_6") (pintype "unspecified"))
      (node (ref "CN14") (pin "1") (pinfunction "1_1") (pintype "unspecified"))
      (node (ref "CN14") (pin "3") (pinfunction "3_3") (pintype "unspecified"))
      (node (ref "CN14") (pin "4") (pinfunction "4_4") (pintype "unspecified"))
      (node (ref "CN15") (pin "3") (pinfunction "3_3") (pintype "unspecified"))
      (node (ref "CN15") (pin "5") (pinfunction "5_5") (pintype "unspecified"))
      (node (ref "CN15") (pin "6") (pinfunction "6_6") (pintype "unspecified"))
      (node (ref "CN16") (pin "3") (pinfunction "3_3") (pintype "unspecified"))
      (node (ref "CN16") (pin "4") (pinfunction "4_4") (pintype "unspecified"))
      (node (ref "CN17") (pin "3") (pinfunction "3_3") (pintype "unspecified"))
      (node (ref "CN17") (pin "4") (pinfunction "4_4") (pintype "unspecified"))
      (node (ref "CN18") (pin "3") (pinfunction "3_3") (pintype "unspecified"))
      (node (ref "CN18") (pin "4") (pinfunction "4_4") (pintype "unspecified"))
      (node (ref "CN19") (pin "3") (pinfunction "3_3") (pintype "unspecified"))
      (node (ref "CN19") (pin "4") (pinfunction "4_4") (pintype "unspecified"))
      (node (ref "CN4") (pin "1") (pinfunction "1_1") (pintype "unspecified"))
      (node (ref "CN4") (pin "4") (pinfunction "4_4") (pintype "unspecified"))
      (node (ref "CN4") (pin "5") (pinfunction "5_5") (pintype "unspecified"))
      (node (ref "CN5") (pin "1") (pinfunction "1_1") (pintype "unspecified"))
      (node (ref "CN5") (pin "4") (pinfunction "4_4") (pintype "unspecified"))
      (node (ref "CN5") (pin "5") (pinfunction "5_5") (pintype "unspecified"))
      (node (ref "CN6") (pin "3") (pinfunction "3_3") (pintype "unspecified"))
      (node (ref "CN6") (pin "4") (pinfunction "4_4") (pintype "unspecified"))
      (node (ref "CN7") (pin "3") (pinfunction "3_3") (pintype "unspecified"))
      (node (ref "CN7") (pin "4") (pinfunction "4_4") (pintype "unspecified"))
      (node (ref "CN8") (pin "3") (pinfunction "3_3") (pintype "unspecified"))
      (node (ref "CN8") (pin "4") (pinfunction "4_4") (pintype "unspecified"))
      (node (ref "CN9") (pin "3") (pinfunction "3_3") (pintype "unspecified"))
      (node (ref "CN9") (pin "4") (pinfunction "4_4") (pintype "unspecified"))
      (node (ref "D1") (pin "3") (pinfunction "A_3") (pintype "unspecified"))
      (node (ref "D2") (pin "3") (pinfunction "A_3") (pintype "unspecified"))
      (node (ref "D4") (pin "2") (pinfunction "A_2") (pintype "unspecified"))
      (node (ref "D5") (pin "2") (pinfunction "A_2") (pintype "unspecified"))
      (node (ref "D6") (pin "1") (pinfunction "1_1") (pintype "input"))
      (node (ref "H1") (pin "1") (pinfunction "1_1") (pintype "unspecified"))
      (node (ref "H2") (pin "1") (pinfunction "1_1") (pintype "unspecified"))
      (node (ref "H3") (pin "1") (pinfunction "1_1") (pintype "unspecified"))
      (node (ref "H4") (pin "3") (pinfunction "3_3") (pintype "unspecified"))
      (node (ref "H5") (pin "1") (pinfunction "1_1") (pintype "unspecified"))
      (node (ref "H6") (pin "2") (pinfunction "2_2") (pintype "unspecified"))
      (node (ref "LED2") (pin "2") (pinfunction "-_2") (pintype "unspecified"))
      (node (ref "LED3") (pin "2") (pinfunction "-_2") (pintype "unspecified"))
      (node (ref "LED4") (pin "2") (pinfunction "-_2") (pintype "unspecified"))
      (node (ref "LED5") (pin "2") (pinfunction "-_2") (pintype "unspecified"))
      (node (ref "Q1") (pin "2") (pinfunction "E_2") (pintype "unspecified"))
      (node (ref "Q2") (pin "2") (pinfunction "E_2") (pintype "unspecified"))
      (node (ref "R13") (pin "1") (pinfunction "1_1") (pintype "input"))
      (node (ref "R15") (pin "1") (pinfunction "1_1") (pintype "input"))
      (node (ref "R22") (pin "1") (pinfunction "1_1") (pintype "input"))
      (node (ref "R4") (pin "2") (pinfunction "2_2") (pintype "input"))
      (node (ref "SW1") (pin "1") (pinfunction "1_1") (pintype "input"))
      (node (ref "U1") (pin "12") (pinfunction "VSSA/VREF-_12") (pintype "unspecified"))
      (node (ref "U1") (pin "18") (pinfunction "VSS_18") (pintype "unspecified"))
      (node (ref "U1") (pin "31") (pinfunction "VSS_31") (pintype "unspecified"))
      (node (ref "U1") (pin "47") (pinfunction "VSS_47") (pintype "unspecified"))
      (node (ref "U1") (pin "63") (pinfunction "VSS_63") (pintype "unspecified"))
      (node (ref "U2") (pin "1") (pinfunction "1_1") (pintype "unspecified"))
      (node (ref "U3") (pin "1") (pinfunction "1_1") (pintype "unspecified"))
      (node (ref "U4") (pin "2") (pinfunction "GND_2") (pintype "input"))
      (node (ref "U4") (pin "8") (pinfunction "STB_8") (pintype "input"))
      (node (ref "U4") (pin "9") (pinfunction "EP_9") (pintype "input"))
      (node (ref "U5") (pin "2") (pinfunction "GND_2") (pintype "input"))
      (node (ref "U5") (pin "8") (pinfunction "STB_8") (pintype "input"))
      (node (ref "U5") (pin "9") (pinfunction "EP_9") (pintype "input"))
      (node (ref "U6") (pin "3") (pinfunction "GND_3") (pintype "unspecified"))
      (node (ref "U7") (pin "6") (pinfunction "GND_6") (pintype "unspecified"))
      (node (ref "U7") (pin "9") (pinfunction "PowerPAD_9") (pintype "unspecified"))
      (node (ref "U8") (pin "6") (pinfunction "GND_6") (pintype "unspecified"))
      (node (ref "U8") (pin "9") (pinfunction "PowerPAD_9") (pintype "unspecified"))
      (node (ref "U9") (pin "1") (pinfunction "ADJ(GND)_1") (pintype "unspecified"))
      (node (ref "USB1") (pin "1") (pinfunction "EP_1") (pintype "input"))
      (node (ref "USB1") (pin "2") (pinfunction "EP_2") (pintype "input"))
      (node (ref "USB1") (pin "3") (pinfunction "EP_3") (pintype "input"))
      (node (ref "USB1") (pin "4") (pinfunction "EP_4") (pintype "input"))
      (node (ref "USB1") (pin "A1") (pinfunction "GND_A1") (pintype "input"))
      (node (ref "USB1") (pin "A12") (pinfunction "GND_A12") (pintype "input"))
      (node (ref "USB1") (pin "B1") (pinfunction "GND_B1") (pintype "input"))
      (node (ref "USB1") (pin "B12") (pinfunction "GND_B12") (pintype "input"))
      (node (ref "USB2") (pin "1") (pinfunction "EP_1") (pintype "input"))
      (node (ref "USB2") (pin "2") (pinfunction "EP_2") (pintype "input"))
      (node (ref "USB2") (pin "3") (pinfunction "EP_3") (pintype "input"))
      (node (ref "USB2") (pin "4") (pinfunction "EP_4") (pintype "input"))
      (node (ref "USB2") (pin "A1") (pinfunction "GND_A1") (pintype "input"))
      (node (ref "USB2") (pin "A12") (pinfunction "GND_A12") (pintype "input"))
      (node (ref "USB2") (pin "B1") (pinfunction "GND_B1") (pintype "input"))
      (node (ref "USB2") (pin "B12") (pinfunction "GND_B12") (pintype "input"))
      (node (ref "X1") (pin "2") (pinfunction "GND_2") (pintype "unspecified"))
      (node (ref "X1") (pin "4") (pinfunction "GND_4") (pintype "unspecified"))
    )
    (net (code "47") (name "Net-(CN5-Pad2)") (class "Default")
      (node (ref "CN5") (pin "2") (pinfunction "2_2") (pintype "unspecified"))
      (node (ref "R2") (pin "2") (pinfunction "2_2") (pintype "input"))
    )
    (net (code "48") (name "Net-(CN5-Pad3)") (class "Default")
      (node (ref "CN5") (pin "3") (pinfunction "3_3") (pintype "unspecified"))
      (node (ref "R3") (pin "2") (pinfunction "2_2") (pintype "input"))
    )
    (net (code "49") (name "Net-(D3-A)") (class "Default")
      (node (ref "BUZZER1") (pin "2") (pinfunction "2_2") (pintype "input"))
      (node (ref "D3") (pin "2") (pinfunction "A_2") (pintype "unspecified"))
      (node (ref "Q1") (pin "3") (pinfunction "C_3") (pintype "unspecified"))
    )
    (net (code "50") (name "Net-(D4-K)") (class "Default")
      (node (ref "C20") (pin "2") (pinfunction "2_2") (pintype "input"))
      (node (ref "D4") (pin "1") (pinfunction "K_1") (pintype "unspecified"))
      (node (ref "L1") (pin "1") (pinfunction "1_1") (pintype "unspecified"))
      (node (ref "U7") (pin "8") (pinfunction "PH_8") (pintype "unspecified"))
    )
    (net (code "51") (name "Net-(D5-K)") (class "Default")
      (node (ref "C24") (pin "2") (pinfunction "2_2") (pintype "input"))
      (node (ref "D5") (pin "1") (pinfunction "K_1") (pintype "unspecified"))
      (node (ref "L2") (pin "1") (pinfunction "1_1") (pintype "unspecified"))
      (node (ref "U8") (pin "8") (pinfunction "PH_8") (pintype "unspecified"))
    )
    (net (code "52") (name "Net-(H4-Pad1)") (class "Default")
      (node (ref "H4") (pin "1") (pinfunction "1_1") (pintype "unspecified"))
      (node (ref "R20") (pin "1") (pinfunction "1_1") (pintype "input"))
    )
    (net (code "53") (name "Net-(LED2-+)") (class "Default")
      (node (ref "LED2") (pin "1") (pinfunction "+_1") (pintype "unspecified"))
      (node (ref "R16") (pin "1") (pinfunction "1_1") (pintype "input"))
    )
    (net (code "54") (name "Net-(LED3-+)") (class "Default")
      (node (ref "LED3") (pin "1") (pinfunction "+_1") (pintype "unspecified"))
      (node (ref "R17") (pin "1") (pinfunction "1_1") (pintype "input"))
    )
    (net (code "55") (name "Net-(LED4-+)") (class "Default")
      (node (ref "LED4") (pin "1") (pinfunction "+_1") (pintype "unspecified"))
      (node (ref "R18") (pin "1") (pinfunction "1_1") (pintype "input"))
    )
    (net (code "56") (name "Net-(LED5-+)") (class "Default")
      (node (ref "LED5") (pin "1") (pinfunction "+_1") (pintype "unspecified"))
      (node (ref "R19") (pin "1") (pinfunction "1_1") (pintype "input"))
    )
    (net (code "57") (name "Net-(Q1-B)") (class "Default")
      (node (ref "Q1") (pin "1") (pinfunction "B_1") (pintype "unspecified"))
      (node (ref "R11") (pin "2") (pinfunction "2_2") (pintype "input"))
    )
    (net (code "58") (name "Net-(Q2-B)") (class "Default")
      (node (ref "Q2") (pin "1") (pinfunction "B_1") (pintype "unspecified"))
      (node (ref "R20") (pin "2") (pinfunction "2_2") (pintype "input"))
    )
    (net (code "59") (name "Net-(Q3-G)") (class "Default")
      (node (ref "Q3") (pin "4") (pinfunction "G_4") (pintype "unspecified"))
      (node (ref "R22") (pin "2") (pinfunction "2_2") (pintype "input"))
    )
    (net (code "60") (name "Net-(U7-BOOT)") (class "Default")
      (node (ref "C20") (pin "1") (pinfunction "1_1") (pintype "input"))
      (node (ref "U7") (pin "1") (pinfunction "BOOT_1") (pintype "unspecified"))
    )
    (net (code "61") (name "Net-(U7-VSENSE)") (class "Default")
      (node (ref "R12") (pin "1") (pinfunction "1_1") (pintype "input"))
      (node (ref "R13") (pin "2") (pinfunction "2_2") (pintype "input"))
      (node (ref "U7") (pin "4") (pinfunction "VSENSE_4") (pintype "unspecified"))
    )
    (net (code "62") (name "Net-(U8-BOOT)") (class "Default")
      (node (ref "C24") (pin "1") (pinfunction "1_1") (pintype "input"))
      (node (ref "U8") (pin "1") (pinfunction "BOOT_1") (pintype "unspecified"))
    )
    (net (code "63") (name "Net-(U8-VSENSE)") (class "Default")
      (node (ref "R14") (pin "1") (pinfunction "1_1") (pintype "input"))
      (node (ref "R15") (pin "2") (pinfunction "2_2") (pintype "input"))
      (node (ref "U8") (pin "4") (pinfunction "VSENSE_4") (pintype "unspecified"))
    )
    (net (code "64") (name "VCC") (class "Default")
      (node (ref "C18") (pin "2") (pinfunction "2_2") (pintype "input"))
      (node (ref "C19") (pin "2") (pinfunction "2_2") (pintype "input"))
      (node (ref "C22") (pin "2") (pinfunction "2_2") (pintype "input"))
      (node (ref "C23") (pin "2") (pinfunction "2_2") (pintype "input"))
      (node (ref "Q3") (pin "1") (pinfunction "S_1") (pintype "unspecified"))
      (node (ref "Q3") (pin "2") (pinfunction "S_2") (pintype "unspecified"))
      (node (ref "Q3") (pin "3") (pinfunction "S_3") (pintype "unspecified"))
      (node (ref "R16") (pin "2") (pinfunction "2_2") (pintype "input"))
      (node (ref "U7") (pin "7") (pinfunction "VIN_7") (pintype "unspecified"))
      (node (ref "U8") (pin "7") (pinfunction "VIN_7") (pintype "unspecified"))
    )
    (net (code "65") (name "VCC3V3") (class "Default")
      (node (ref "BUZZER1") (pin "1") (pinfunction "+_1") (pintype "input"))
      (node (ref "C13") (pin "1") (pinfunction "1_1") (pintype "input"))
      (node (ref "C15") (pin "1") (pinfunction "1_1") (pintype "input"))
      (node (ref "C16") (pin "2") (pinfunction "2_2") (pintype "input"))
      (node (ref "C26") (pin "1") (pinfunction "1_1") (pintype "input"))
      (node (ref "C3") (pin "1") (pinfunction "1_1") (pintype "input"))
      (node (ref "C4") (pin "2") (pinfunction "2_2") (pintype "input"))
      (node (ref "C5") (pin "2") (pinfunction "2_2") (pintype "input"))
      (node (ref "C6") (pin "2") (pinfunction "2_2") (pintype "input"))
      (node (ref "C7") (pin "2") (pinfunction "2_2") (pintype "input"))
      (node (ref "C8") (pin "2") (pinfunction "2_2") (pintype "input"))
      (node (ref "C9") (pin "2") (pinfunction "2_2") (pintype "input"))
      (node (ref "CN15") (pin "4") (pinfunction "4_4") (pintype "unspecified"))
      (node (ref "D3") (pin "1") (pinfunction "K_1") (pintype "unspecified"))
      (node (ref "H5") (pin "2") (pinfunction "2_2") (pintype "unspecified"))
      (node (ref "H6") (pin "1") (pinfunction "1_1") (pintype "unspecified"))
      (node (ref "R1") (pin "2") (pinfunction "2_2") (pintype "input"))
      (node (ref "R19") (pin "2") (pinfunction "2_2") (pintype "input"))
      (node (ref "R21") (pin "2") (pinfunction "2_2") (pintype "input"))
      (node (ref "SW2") (pin "1") (pinfunction "1_1") (pintype "input"))
      (node (ref "U1") (pin "1") (pinfunction "VBAT_1") (pintype "unspecified"))
      (node (ref "U1") (pin "13") (pinfunction "VDDA/VREF+_13") (pintype "unspecified"))
      (node (ref "U1") (pin "19") (pinfunction "VDD_19") (pintype "unspecified"))
      (node (ref "U1") (pin "32") (pinfunction "VDD_32") (pintype "unspecified"))
      (node (ref "U1") (pin "48") (pinfunction "VDD_48") (pintype "unspecified"))
      (node (ref "U1") (pin "64") (pinfunction "VDD_64") (pintype "unspecified"))
      (node (ref "U4") (pin "5") (pinfunction "VIO_5") (pintype "input"))
      (node (ref "U5") (pin "5") (pinfunction "VIO_5") (pintype "input"))
      (node (ref "U6") (pin "5") (pinfunction "VCC_5") (pintype "unspecified"))
      (node (ref "U6") (pin "8") (pinfunction "V3_8") (pintype "unspecified"))
      (node (ref "U9") (pin "2") (pinfunction "VOUT(TAB)_2") (pintype "unspecified"))
    )
    (net (code "66") (name "unconnected-(BUZZER1-Pad3)") (class "Default")
      (node (ref "BUZZER1") (pin "3") (pinfunction "3_3") (pintype "input+no_connect"))
    )
    (net (code "67") (name "unconnected-(BUZZER1-Pad4)") (class "Default")
      (node (ref "BUZZER1") (pin "4") (pinfunction "4_4") (pintype "input+no_connect"))
    )
    (net (code "68") (name "unconnected-(U1-PA4-Pad20)") (class "Default")
      (node (ref "U1") (pin "20") (pinfunction "PA4_20") (pintype "unspecified"))
    )
    (net (code "69") (name "unconnected-(U1-PA5-Pad21)") (class "Default")
      (node (ref "U1") (pin "21") (pinfunction "PA5_21") (pintype "unspecified"))
    )
    (net (code "70") (name "unconnected-(U1-PA6-Pad22)") (class "Default")
      (node (ref "U1") (pin "22") (pinfunction "PA6_22") (pintype "unspecified"))
    )
    (net (code "71") (name "unconnected-(U1-PA7-Pad23)") (class "Default")
      (node (ref "U1") (pin "23") (pinfunction "PA7_23") (pintype "unspecified"))
    )
    (net (code "72") (name "unconnected-(U1-PA8-Pad41)") (class "Default")
      (node (ref "U1") (pin "41") (pinfunction "PA8_41") (pintype "unspecified"))
    )
    (net (code "73") (name "unconnected-(U1-PB0-Pad26)") (class "Default")
      (node (ref "U1") (pin "26") (pinfunction "PB0_26") (pintype "unspecified"))
    )
    (net (code "74") (name "unconnected-(U1-PB1-Pad27)") (class "Default")
      (node (ref "U1") (pin "27") (pinfunction "PB1_27") (pintype "unspecified"))
    )
    (net (code "75") (name "unconnected-(U1-PB2-Pad28)") (class "Default")
      (node (ref "U1") (pin "28") (pinfunction "PB2_28") (pintype "unspecified"))
    )
    (net (code "76") (name "unconnected-(U1-PC0-Pad8)") (class "Default")
      (node (ref "U1") (pin "8") (pinfunction "PC0_8") (pintype "unspecified"))
    )
    (net (code "77") (name "unconnected-(U1-PC1-Pad9)") (class "Default")
      (node (ref "U1") (pin "9") (pinfunction "PC1_9") (pintype "unspecified"))
    )
    (net (code "78") (name "unconnected-(U1-PC2-Pad10)") (class "Default")
      (node (ref "U1") (pin "10") (pinfunction "PC2_10") (pintype "unspecified"))
    )
    (net (code "79") (name "unconnected-(U1-PC3-Pad11)") (class "Default")
      (node (ref "U1") (pin "11") (pinfunction "PC3_11") (pintype "unspecified"))
    )
    (net (code "80") (name "unconnected-(U1-PC4-Pad24)") (class "Default")
      (node (ref "U1") (pin "24") (pinfunction "PC4_24") (pintype "unspecified"))
    )
    (net (code "81") (name "unconnected-(U1-PC6-Pad37)") (class "Default")
      (node (ref "U1") (pin "37") (pinfunction "PC6_37") (pintype "unspecified"))
    )
    (net (code "82") (name "unconnected-(U1-PC7-Pad38)") (class "Default")
      (node (ref "U1") (pin "38") (pinfunction "PC7_38") (pintype "unspecified"))
    )
    (net (code "83") (name "unconnected-(U1-PC8-Pad39)") (class "Default")
      (node (ref "U1") (pin "39") (pinfunction "PC8_39") (pintype "unspecified"))
    )
    (net (code "84") (name "unconnected-(U1-PC9-Pad40)") (class "Default")
      (node (ref "U1") (pin "40") (pinfunction "PC9_40") (pintype "unspecified"))
    )
    (net (code "85") (name "unconnected-(U1-PC10-Pad51)") (class "Default")
      (node (ref "U1") (pin "51") (pinfunction "PC10_51") (pintype "unspecified"))
    )
    (net (code "86") (name "unconnected-(U1-PC13-Pad2)") (class "Default")
      (node (ref "U1") (pin "2") (pinfunction "PC13_2") (pintype "unspecified"))
    )
    (net (code "87") (name "unconnected-(U6-RTS#-Pad4)") (class "Default")
      (node (ref "U6") (pin "4") (pinfunction "RTS#_4") (pintype "unspecified+no_connect"))
    )
    (net (code "88") (name "unconnected-(U7-ENA-Pad5)") (class "Default")
      (node (ref "U7") (pin "5") (pinfunction "ENA_5") (pintype "unspecified+no_connect"))
    )
    (net (code "89") (name "unconnected-(U7-NC-Pad2)") (class "Default")
      (node (ref "U7") (pin "2") (pinfunction "NC_2") (pintype "unspecified+no_connect"))
    )
    (net (code "90") (name "unconnected-(U7-NC-Pad3)") (class "Default")
      (node (ref "U7") (pin "3") (pinfunction "NC_3") (pintype "unspecified+no_connect"))
    )
    (net (code "91") (name "unconnected-(U8-ENA-Pad5)") (class "Default")
      (node (ref "U8") (pin "5") (pinfunction "ENA_5") (pintype "unspecified+no_connect"))
    )
    (net (code "92") (name "unconnected-(U8-NC-Pad2)") (class "Default")
      (node (ref "U8") (pin "2") (pinfunction "NC_2") (pintype "unspecified+no_connect"))
    )
    (net (code "93") (name "unconnected-(U8-NC-Pad3)") (class "Default")
      (node (ref "U8") (pin "3") (pinfunction "NC_3") (pintype "unspecified+no_connect"))
    )
    (net (code "94") (name "unconnected-(USB1-CC1-PadA5)") (class "Default")
      (node (ref "USB1") (pin "A5") (pinfunction "CC1_A5") (pintype "input+no_connect"))
    )
    (net (code "95") (name "unconnected-(USB1-CC2-PadB5)") (class "Default")
      (node (ref "USB1") (pin "B5") (pinfunction "CC2_B5") (pintype "input+no_connect"))
    )
    (net (code "96") (name "unconnected-(USB1-SBUS1-PadA8)") (class "Default")
      (node (ref "USB1") (pin "A8") (pinfunction "SBUS1_A8") (pintype "input+no_connect"))
    )
    (net (code "97") (name "unconnected-(USB1-SBUS2-PadB8)") (class "Default")
      (node (ref "USB1") (pin "B8") (pinfunction "SBUS2_B8") (pintype "input+no_connect"))
    )
    (net (code "98") (name "unconnected-(USB2-CC1-PadA5)") (class "Default")
      (node (ref "USB2") (pin "A5") (pinfunction "CC1_A5") (pintype "input+no_connect"))
    )
    (net (code "99") (name "unconnected-(USB2-CC2-PadB5)") (class "Default")
      (node (ref "USB2") (pin "B5") (pinfunction "CC2_B5") (pintype "input+no_connect"))
    )
    (net (code "100") (name "unconnected-(USB2-SBUS1-PadA8)") (class "Default")
      (node (ref "USB2") (pin "A8") (pinfunction "SBUS1_A8") (pintype "input+no_connect"))
    )
    (net (code "101") (name "unconnected-(USB2-SBUS2-PadB8)") (class "Default")
      (node (ref "USB2") (pin "B8") (pinfunction "SBUS2_B8") (pintype "input+no_connect"))
    )
  )
)
